# Connectors.net
KiCad netlist of a schematic drawn in Altium Designer
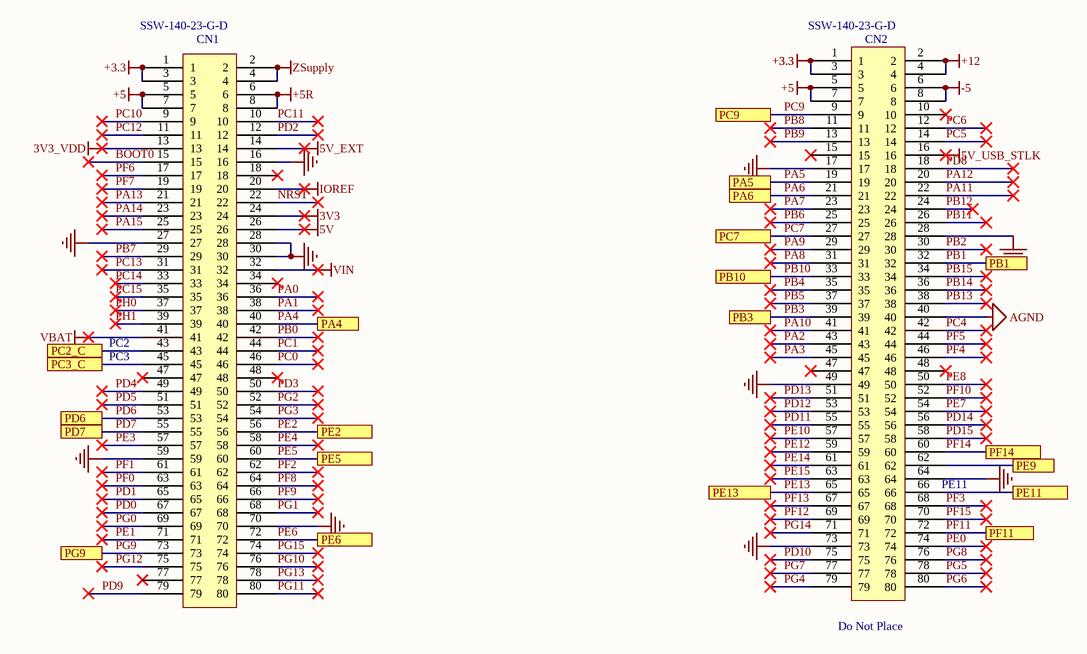
[diagram p0: Connectors.SchDoc]

(export (version "E")
  (design (tool "Eeschema 10.0.6"))
  (components
    (comp (ref "CN1")
      (value "Do Not Place")
      (footprint "SSW-140-23-G-D")
      (description "Conn Socket Strip SKT 80 POS 2.54mm Solder ST Thru-Hole")
      (fields
        (field (name "SUPPLIER PART NUMBER 1") "SSW-140-23-G-D")
        (field (name "MANUFACTURER") "Samtec")
        (field (name "MANUFACTURER PART NUMBER") "SSW-140-23-G-D")
      )
      (libsource (lib "ZLS_Schematic_lib") (part "SSW-140-23-G-D"))
    )
    (comp (ref "CN2")
      (value "Do Not Place")
      (footprint "SSW-140-23-G-D")
      (description "Conn Socket Strip SKT 80 POS 2.54mm Solder ST Thru-Hole")
      (fields
        (field (name "SUPPLIER PART NUMBER 1") "SSW-140-23-G-D")
        (field (name "MANUFACTURER") "Samtec")
        (field (name "MANUFACTURER PART NUMBER") "SSW-140-23-G-D")
      )
      (libsource (lib "ZLS_Schematic_lib") (part "SSW-140-23-G-D"))
    )
  )
  (nets
    (net (code "1") (name "+3.3") (class "Default")
      (node (ref "CN1") (pin "1") (pinfunction "1_1") (pintype "passive"))
      (node (ref "CN1") (pin "3") (pinfunction "3_3") (pintype "passive"))
      (node (ref "CN2") (pin "1") (pinfunction "1_1") (pintype "passive"))
      (node (ref "CN2") (pin "3") (pinfunction "3_3") (pintype "passive"))
    )
    (net (code "2") (name "+5") (class "Default")
      (node (ref "CN1") (pin "5") (pinfunction "5_5") (pintype "passive"))
      (node (ref "CN1") (pin "7") (pinfunction "7_7") (pintype "passive"))
      (node (ref "CN2") (pin "5") (pinfunction "5_5") (pintype "passive"))
      (node (ref "CN2") (pin "7") (pinfunction "7_7") (pintype "passive"))
    )
    (net (code "3") (name "+5R") (class "Default")
      (node (ref "CN1") (pin "6") (pinfunction "6_6") (pintype "passive"))
      (node (ref "CN1") (pin "8") (pinfunction "8_8") (pintype "passive"))
    )
    (net (code "4") (name "+12") (class "Default")
      (node (ref "CN2") (pin "2") (pinfunction "2_2") (pintype "passive"))
      (node (ref "CN2") (pin "4") (pinfunction "4_4") (pintype "passive"))
    )
    (net (code "5") (name "-5") (class "Default")
      (node (ref "CN2") (pin "6") (pinfunction "6_6") (pintype "passive"))
      (node (ref "CN2") (pin "8") (pinfunction "8_8") (pintype "passive"))
    )
    (net (code "6") (name "/BOOT0") (class "Default")
      (node (ref "CN1") (pin "15") (pinfunction "15_15") (pintype "passive+no_connect"))
    )
    (net (code "7") (name "/NRST") (class "Default")
      (node (ref "CN1") (pin "22") (pinfunction "22_22") (pintype "passive+no_connect"))
    )
    (net (code "8") (name "/PA0") (class "Default")
      (node (ref "CN1") (pin "36") (pinfunction "36_36") (pintype "passive+no_connect"))
    )
    (net (code "9") (name "/PA1") (class "Default")
      (node (ref "CN1") (pin "38") (pinfunction "38_38") (pintype "passive+no_connect"))
    )
    (net (code "10") (name "/PA2") (class "Default")
      (node (ref "CN2") (pin "43") (pinfunction "43_43") (pintype "passive+no_connect"))
    )
    (net (code "11") (name "/PA3") (class "Default")
      (node (ref "CN2") (pin "45") (pinfunction "45_45") (pintype "passive+no_connect"))
    )
    (net (code "12") (name "/PA4") (class "Default")
      (node (ref "CN1") (pin "40") (pinfunction "40_40") (pintype "passive"))
    )
    (net (code "13") (name "/PA5") (class "Default")
      (node (ref "CN2") (pin "19") (pinfunction "19_19") (pintype "passive"))
    )
    (net (code "14") (name "/PA6") (class "Default")
      (node (ref "CN2") (pin "21") (pinfunction "21_21") (pintype "passive"))
    )
    (net (code "15") (name "/PA7") (class "Default")
      (node (ref "CN2") (pin "23") (pinfunction "23_23") (pintype "passive+no_connect"))
    )
    (net (code "16") (name "/PA8") (class "Default")
      (node (ref "CN2") (pin "31") (pinfunction "31_31") (pintype "passive+no_connect"))
    )
    (net (code "17") (name "/PA9") (class "Default")
      (node (ref "CN2") (pin "29") (pinfunction "29_29") (pintype "passive+no_connect"))
    )
    (net (code "18") (name "/PA10") (class "Default")
      (node (ref "CN2") (pin "41") (pinfunction "41_41") (pintype "passive+no_connect"))
    )
    (net (code "19") (name "/PA11") (class "Default")
      (node (ref "CN2") (pin "22") (pinfunction "22_22") (pintype "passive+no_connect"))
    )
    (net (code "20") (name "/PA12") (class "Default")
      (node (ref "CN2") (pin "20") (pinfunction "20_20") (pintype "passive+no_connect"))
    )
    (net (code "21") (name "/PA13") (class "Default")
      (node (ref "CN1") (pin "21") (pinfunction "21_21") (pintype "passive+no_connect"))
    )
    (net (code "22") (name "/PA14") (class "Default")
      (node (ref "CN1") (pin "23") (pinfunction "23_23") (pintype "passive+no_connect"))
    )
    (net (code "23") (name "/PA15") (class "Default")
      (node (ref "CN1") (pin "25") (pinfunction "25_25") (pintype "passive+no_connect"))
    )
    (net (code "24") (name "/PB0") (class "Default")
      (node (ref "CN1") (pin "42") (pinfunction "42_42") (pintype "passive+no_connect"))
    )
    (net (code "25") (name "/PB1") (class "Default")
      (node (ref "CN2") (pin "32") (pinfunction "32_32") (pintype "passive"))
    )
    (net (code "26") (name "/PB2") (class "Default")
      (node (ref "CN2") (pin "30") (pinfunction "30_30") (pintype "passive+no_connect"))
    )
    (net (code "27") (name "/PB3") (class "Default")
      (node (ref "CN2") (pin "39") (pinfunction "39_39") (pintype "passive"))
    )
    (net (code "28") (name "/PB4") (class "Default")
      (node (ref "CN2") (pin "35") (pinfunction "35_35") (pintype "passive+no_connect"))
    )
    (net (code "29") (name "/PB5") (class "Default")
      (node (ref "CN2") (pin "37") (pinfunction "37_37") (pintype "passive+no_connect"))
    )
    (net (code "30") (name "/PB6") (class "Default")
      (node (ref "CN2") (pin "25") (pinfunction "25_25") (pintype "passive+no_connect"))
    )
    (net (code "31") (name "/PB7") (class "Default")
      (node (ref "CN1") (pin "29") (pinfunction "29_29") (pintype "passive+no_connect"))
    )
    (net (code "32") (name "/PB8") (class "Default")
      (node (ref "CN2") (pin "11") (pinfunction "11_11") (pintype "passive+no_connect"))
    )
    (net (code "33") (name "/PB9") (class "Default")
      (node (ref "CN2") (pin "13") (pinfunction "13_13") (pintype "passive+no_connect"))
    )
    (net (code "34") (name "/PB10") (class "Default")
      (node (ref "CN2") (pin "33") (pinfunction "33_33") (pintype "passive"))
    )
    (net (code "35") (name "/PB11") (class "Default")
      (node (ref "CN2") (pin "26") (pinfunction "26_26") (pintype "passive+no_connect"))
    )
    (net (code "36") (name "/PB12") (class "Default")
      (node (ref "CN2") (pin "24") (pinfunction "24_24") (pintype "passive+no_connect"))
    )
    (net (code "37") (name "/PB13") (class "Default")
      (node (ref "CN2") (pin "38") (pinfunction "38_38") (pintype "passive+no_connect"))
    )
    (net (code "38") (name "/PB14") (class "Default")
      (node (ref "CN2") (pin "36") (pinfunction "36_36") (pintype "passive+no_connect"))
    )
    (net (code "39") (name "/PB15") (class "Default")
      (node (ref "CN2") (pin "34") (pinfunction "34_34") (pintype "passive+no_connect"))
    )
    (net (code "40") (name "/PC0") (class "Default")
      (node (ref "CN1") (pin "46") (pinfunction "46_46") (pintype "passive+no_connect"))
    )
    (net (code "41") (name "/PC1") (class "Default")
      (node (ref "CN1") (pin "44") (pinfunction "44_44") (pintype "passive+no_connect"))
    )
    (net (code "42") (name "/PC2_C") (class "Default")
      (node (ref "CN1") (pin "43") (pinfunction "43_43") (pintype "passive"))
    )
    (net (code "43") (name "/PC3_C") (class "Default")
      (node (ref "CN1") (pin "45") (pinfunction "45_45") (pintype "passive"))
    )
    (net (code "44") (name "/PC4") (class "Default")
      (node (ref "CN2") (pin "42") (pinfunction "42_42") (pintype "passive+no_connect"))
    )
    (net (code "45") (name "/PC5") (class "Default")
      (node (ref "CN2") (pin "14") (pinfunction "14_14") (pintype "passive+no_connect"))
    )
    (net (code "46") (name "/PC6") (class "Default")
      (node (ref "CN2") (pin "12") (pinfunction "12_12") (pintype "passive+no_connect"))
    )
    (net (code "47") (name "/PC7") (class "Default")
      (node (ref "CN2") (pin "27") (pinfunction "27_27") (pintype "passive"))
    )
    (net (code "48") (name "/PC9") (class "Default")
      (node (ref "CN2") (pin "9") (pinfunction "9_9") (pintype "passive"))
    )
    (net (code "49") (name "/PC10") (class "Default")
      (node (ref "CN1") (pin "9") (pinfunction "9_9") (pintype "passive+no_connect"))
    )
    (net (code "50") (name "/PC11") (class "Default")
      (node (ref "CN1") (pin "10") (pinfunction "10_10") (pintype "passive+no_connect"))
    )
    (net (code "51") (name "/PC12") (class "Default")
      (node (ref "CN1") (pin "11") (pinfunction "11_11") (pintype "passive+no_connect"))
    )
    (net (code "52") (name "/PC13") (class "Default")
      (node (ref "CN1") (pin "31") (pinfunction "31_31") (pintype "passive+no_connect"))
    )
    (net (code "53") (name "/PC14") (class "Default")
      (node (ref "CN1") (pin "33") (pinfunction "33_33") (pintype "passive+no_connect"))
    )
    (net (code "54") (name "/PC15") (class "Default")
      (node (ref "CN1") (pin "35") (pinfunction "35_35") (pintype "passive+no_connect"))
    )
    (net (code "55") (name "/PD0") (class "Default")
      (node (ref "CN1") (pin "67") (pinfunction "67_67") (pintype "passive+no_connect"))
    )
    (net (code "56") (name "/PD1") (class "Default")
      (node (ref "CN1") (pin "65") (pinfunction "65_65") (pintype "passive+no_connect"))
    )
    (net (code "57") (name "/PD2") (class "Default")
      (node (ref "CN1") (pin "12") (pinfunction "12_12") (pintype "passive+no_connect"))
    )
    (net (code "58") (name "/PD3") (class "Default")
      (node (ref "CN1") (pin "50") (pinfunction "50_50") (pintype "passive+no_connect"))
    )
    (net (code "59") (name "/PD4") (class "Default")
      (node (ref "CN1") (pin "49") (pinfunction "49_49") (pintype "passive+no_connect"))
    )
    (net (code "60") (name "/PD5") (class "Default")
      (node (ref "CN1") (pin "51") (pinfunction "51_51") (pintype "passive+no_connect"))
    )
    (net (code "61") (name "/PD6") (class "Default")
      (node (ref "CN1") (pin "53") (pinfunction "53_53") (pintype "passive"))
    )
    (net (code "62") (name "/PD7") (class "Default")
      (node (ref "CN1") (pin "55") (pinfunction "55_55") (pintype "passive"))
    )
    (net (code "63") (name "/PD8") (class "Default")
      (node (ref "CN2") (pin "18") (pinfunction "18_18") (pintype "passive+no_connect"))
    )
    (net (code "64") (name "/PD9") (class "Default")
      (node (ref "CN1") (pin "79") (pinfunction "79_79") (pintype "passive+no_connect"))
    )
    (net (code "65") (name "/PD10") (class "Default")
      (node (ref "CN2") (pin "75") (pinfunction "75_75") (pintype "passive+no_connect"))
    )
    (net (code "66") (name "/PD11") (class "Default")
      (node (ref "CN2") (pin "55") (pinfunction "55_55") (pintype "passive+no_connect"))
    )
    (net (code "67") (name "/PD12") (class "Default")
      (node (ref "CN2") (pin "53") (pinfunction "53_53") (pintype "passive+no_connect"))
    )
    (net (code "68") (name "/PD13") (class "Default")
      (node (ref "CN2") (pin "51") (pinfunction "51_51") (pintype "passive+no_connect"))
    )
    (net (code "69") (name "/PD14") (class "Default")
      (node (ref "CN2") (pin "56") (pinfunction "56_56") (pintype "passive+no_connect"))
    )
    (net (code "70") (name "/PD15") (class "Default")
      (node (ref "CN2") (pin "58") (pinfunction "58_58") (pintype "passive+no_connect"))
    )
    (net (code "71") (name "/PE0") (class "Default")
      (node (ref "CN2") (pin "74") (pinfunction "74_74") (pintype "passive+no_connect"))
    )
    (net (code "72") (name "/PE1") (class "Default")
      (node (ref "CN1") (pin "71") (pinfunction "71_71") (pintype "passive+no_connect"))
    )
    (net (code "73") (name "/PE2") (class "Default")
      (node (ref "CN1") (pin "56") (pinfunction "56_56") (pintype "passive"))
    )
    (net (code "74") (name "/PE3") (class "Default")
      (node (ref "CN1") (pin "57") (pinfunction "57_57") (pintype "passive+no_connect"))
    )
    (net (code "75") (name "/PE4") (class "Default")
      (node (ref "CN1") (pin "58") (pinfunction "58_58") (pintype "passive+no_connect"))
    )
    (net (code "76") (name "/PE5") (class "Default")
      (node (ref "CN1") (pin "60") (pinfunction "60_60") (pintype "passive"))
    )
    (net (code "77") (name "/PE6") (class "Default")
      (node (ref "CN1") (pin "72") (pinfunction "72_72") (pintype "passive"))
    )
    (net (code "78") (name "/PE7") (class "Default")
      (node (ref "CN2") (pin "54") (pinfunction "54_54") (pintype "passive+no_connect"))
    )
    (net (code "79") (name "/PE8") (class "Default")
      (node (ref "CN2") (pin "50") (pinfunction "50_50") (pintype "passive+no_connect"))
    )
    (net (code "80") (name "/PE9") (class "Default")
      (node (ref "CN2") (pin "62") (pinfunction "62_62") (pintype "passive"))
    )
    (net (code "81") (name "/PE10") (class "Default")
      (node (ref "CN2") (pin "57") (pinfunction "57_57") (pintype "passive+no_connect"))
    )
    (net (code "82") (name "/PE11") (class "Default")
      (node (ref "CN2") (pin "66") (pinfunction "66_66") (pintype "passive"))
    )
    (net (code "83") (name "/PE12") (class "Default")
      (node (ref "CN2") (pin "59") (pinfunction "59_59") (pintype "passive+no_connect"))
    )
    (net (code "84") (name "/PE13") (class "Default")
      (node (ref "CN2") (pin "65") (pinfunction "65_65") (pintype "passive"))
    )
    (net (code "85") (name "/PE14") (class "Default")
      (node (ref "CN2") (pin "61") (pinfunction "61_61") (pintype "passive+no_connect"))
    )
    (net (code "86") (name "/PE15") (class "Default")
      (node (ref "CN2") (pin "63") (pinfunction "63_63") (pintype "passive+no_connect"))
    )
    (net (code "87") (name "/PF0") (class "Default")
      (node (ref "CN1") (pin "63") (pinfunction "63_63") (pintype "passive+no_connect"))
    )
    (net (code "88") (name "/PF1") (class "Default")
      (node (ref "CN1") (pin "61") (pinfunction "61_61") (pintype "passive+no_connect"))
    )
    (net (code "89") (name "/PF2") (class "Default")
      (node (ref "CN1") (pin "62") (pinfunction "62_62") (pintype "passive+no_connect"))
    )
    (net (code "90") (name "/PF3") (class "Default")
      (node (ref "CN2") (pin "68") (pinfunction "68_68") (pintype "passive+no_connect"))
    )
    (net (code "91") (name "/PF4") (class "Default")
      (node (ref "CN2") (pin "46") (pinfunction "46_46") (pintype "passive+no_connect"))
    )
    (net (code "92") (name "/PF5") (class "Default")
      (node (ref "CN2") (pin "44") (pinfunction "44_44") (pintype "passive+no_connect"))
    )
    (net (code "93") (name "/PF6") (class "Default")
      (node (ref "CN1") (pin "17") (pinfunction "17_17") (pintype "passive+no_connect"))
    )
    (net (code "94") (name "/PF7") (class "Default")
      (node (ref "CN1") (pin "19") (pinfunction "19_19") (pintype "passive+no_connect"))
    )
    (net (code "95") (name "/PF8") (class "Default")
      (node (ref "CN1") (pin "64") (pinfunction "64_64") (pintype "passive+no_connect"))
    )
    (net (code "96") (name "/PF9") (class "Default")
      (node (ref "CN1") (pin "66") (pinfunction "66_66") (pintype "passive+no_connect"))
    )
    (net (code "97") (name "/PF10") (class "Default")
      (node (ref "CN2") (pin "52") (pinfunction "52_52") (pintype "passive+no_connect"))
    )
    (net (code "98") (name "/PF11") (class "Default")
      (node (ref "CN2") (pin "72") (pinfunction "72_72") (pintype "passive"))
    )
    (net (code "99") (name "/PF12") (class "Default")
      (node (ref "CN2") (pin "69") (pinfunction "69_69") (pintype "passive+no_connect"))
    )
    (net (code "100") (name "/PF13") (class "Default")
      (node (ref "CN2") (pin "67") (pinfunction "67_67") (pintype "passive+no_connect"))
    )
    (net (code "101") (name "/PF14") (class "Default")
      (node (ref "CN2") (pin "60") (pinfunction "60_60") (pintype "passive"))
    )
    (net (code "102") (name "/PF15") (class "Default")
      (node (ref "CN2") (pin "70") (pinfunction "70_70") (pintype "passive+no_connect"))
    )
    (net (code "103") (name "/PG0") (class "Default")
      (node (ref "CN1") (pin "69") (pinfunction "69_69") (pintype "passive+no_connect"))
    )
    (net (code "104") (name "/PG1") (class "Default")
      (node (ref "CN1") (pin "68") (pinfunction "68_68") (pintype "passive+no_connect"))
    )
    (net (code "105") (name "/PG2") (class "Default")
      (node (ref "CN1") (pin "52") (pinfunction "52_52") (pintype "passive+no_connect"))
    )
    (net (code "106") (name "/PG3") (class "Default")
      (node (ref "CN1") (pin "54") (pinfunction "54_54") (pintype "passive+no_connect"))
    )
    (net (code "107") (name "/PG4") (class "Default")
      (node (ref "CN2") (pin "79") (pinfunction "79_79") (pintype "passive+no_connect"))
    )
    (net (code "108") (name "/PG5") (class "Default")
      (node (ref "CN2") (pin "78") (pinfunction "78_78") (pintype "passive+no_connect"))
    )
    (net (code "109") (name "/PG6") (class "Default")
      (node (ref "CN2") (pin "80") (pinfunction "80_80") (pintype "passive+no_connect"))
    )
    (net (code "110") (name "/PG7") (class "Default")
      (node (ref "CN2") (pin "77") (pinfunction "77_77") (pintype "passive+no_connect"))
    )
    (net (code "111") (name "/PG8") (class "Default")
      (node (ref "CN2") (pin "76") (pinfunction "76_76") (pintype "passive+no_connect"))
    )
    (net (code "112") (name "/PG9") (class "Default")
      (node (ref "CN1") (pin "73") (pinfunction "73_73") (pintype "passive"))
    )
    (net (code "113") (name "/PG10") (class "Default")
      (node (ref "CN1") (pin "76") (pinfunction "76_76") (pintype "passive+no_connect"))
    )
    (net (code "114") (name "/PG11") (class "Default")
      (node (ref "CN1") (pin "80") (pinfunction "80_80") (pintype "passive+no_connect"))
    )
    (net (code "115") (name "/PG12") (class "Default")
      (node (ref "CN1") (pin "75") (pinfunction "75_75") (pintype "passive+no_connect"))
    )
    (net (code "116") (name "/PG13") (class "Default")
      (node (ref "CN1") (pin "78") (pinfunction "78_78") (pintype "passive+no_connect"))
    )
    (net (code "117") (name "/PG14") (class "Default")
      (node (ref "CN2") (pin "71") (pinfunction "71_71") (pintype "passive+no_connect"))
    )
    (net (code "118") (name "/PG15") (class "Default")
      (node (ref "CN1") (pin "74") (pinfunction "74_74") (pintype "passive+no_connect"))
    )
    (net (code "119") (name "/PH0") (class "Default")
      (node (ref "CN1") (pin "37") (pinfunction "37_37") (pintype "passive+no_connect"))
    )
    (net (code "120") (name "/PH1") (class "Default")
      (node (ref "CN1") (pin "39") (pinfunction "39_39") (pintype "passive+no_connect"))
    )
    (net (code "121") (name "3V3") (class "Default")
      (node (ref "CN1") (pin "24") (pinfunction "24_24") (pintype "passive"))
    )
    (net (code "122") (name "3V3_VDD") (class "Default")
      (node (ref "CN1") (pin "13") (pinfunction "13_13") (pintype "passive"))
    )
    (net (code "123") (name "5V") (class "Default")
      (node (ref "CN1") (pin "26") (pinfunction "26_26") (pintype "passive"))
    )
    (net (code "124") (name "5V_EXT") (class "Default")
      (node (ref "CN1") (pin "14") (pinfunction "14_14") (pintype "passive"))
    )
    (net (code "125") (name "5V_USB_STLK") (class "Default")
      (node (ref "CN2") (pin "16") (pinfunction "16_16") (pintype "passive"))
    )
    (net (code "126") (name "AGND") (class "Default")
      (node (ref "CN2") (pin "40") (pinfunction "40_40") (pintype "passive"))
    )
    (net (code "127") (name "GND") (class "Default")
      (node (ref "CN1") (pin "16") (pinfunction "16_16") (pintype "passive"))
      (node (ref "CN1") (pin "27") (pinfunction "27_27") (pintype "passive"))
      (node (ref "CN1") (pin "28") (pinfunction "28_28") (pintype "passive"))
      (node (ref "CN1") (pin "30") (pinfunction "30_30") (pintype "passive"))
      (node (ref "CN1") (pin "59") (pinfunction "59_59") (pintype "passive"))
      (node (ref "CN1") (pin "70") (pinfunction "70_70") (pintype "passive"))
      (node (ref "CN2") (pin "17") (pinfunction "17_17") (pintype "passive"))
      (node (ref "CN2") (pin "28") (pinfunction "28_28") (pintype "passive"))
      (node (ref "CN2") (pin "49") (pinfunction "49_49") (pintype "passive"))
      (node (ref "CN2") (pin "64") (pinfunction "64_64") (pintype "passive"))
      (node (ref "CN2") (pin "73") (pinfunction "73_73") (pintype "passive"))
    )
    (net (code "128") (name "IOREF") (class "Default")
      (node (ref "CN1") (pin "20") (pinfunction "20_20") (pintype "passive"))
    )
    (net (code "129") (name "VBAT") (class "Default")
      (node (ref "CN1") (pin "41") (pinfunction "41_41") (pintype "passive"))
    )
    (net (code "130") (name "VIN") (class "Default")
      (node (ref "CN1") (pin "32") (pinfunction "32_32") (pintype "passive"))
    )
    (net (code "131") (name "ZSupply") (class "Default")
      (node (ref "CN1") (pin "2") (pinfunction "2_2") (pintype "passive"))
      (node (ref "CN1") (pin "4") (pinfunction "4_4") (pintype "passive"))
    )
    (net (code "132") (name "unconnected-(CN1-Pad18)") (class "Default")
      (node (ref "CN1") (pin "18") (pinfunction "18_18") (pintype "passive+no_connect"))
    )
    (net (code "133") (name "unconnected-(CN1-Pad34)") (class "Default")
      (node (ref "CN1") (pin "34") (pinfunction "34_34") (pintype "passive+no_connect"))
    )
    (net (code "134") (name "unconnected-(CN1-Pad47)") (class "Default")
      (node (ref "CN1") (pin "47") (pinfunction "47_47") (pintype "passive+no_connect"))
    )
    (net (code "135") (name "unconnected-(CN1-Pad48)") (class "Default")
      (node (ref "CN1") (pin "48") (pinfunction "48_48") (pintype "passive+no_connect"))
    )
    (net (code "136") (name "unconnected-(CN1-Pad77)") (class "Default")
      (node (ref "CN1") (pin "77") (pinfunction "77_77") (pintype "passive+no_connect"))
    )
    (net (code "137") (name "unconnected-(CN2-Pad10)") (class "Default")
      (node (ref "CN2") (pin "10") (pinfunction "10_10") (pintype "passive+no_connect"))
    )
    (net (code "138") (name "unconnected-(CN2-Pad15)") (class "Default")
      (node (ref "CN2") (pin "15") (pinfunction "15_15") (pintype "passive+no_connect"))
    )
    (net (code "139") (name "unconnected-(CN2-Pad47)") (class "Default")
      (node (ref "CN2") (pin "47") (pinfunction "47_47") (pintype "passive+no_connect"))
    )
    (net (code "140") (name "unconnected-(CN2-Pad48)") (class "Default")
      (node (ref "CN2") (pin "48") (pinfunction "48_48") (pintype "passive+no_connect"))
    )
  )
)
